# LEDs.net
KiCad netlist of a schematic drawn in Altium Designer
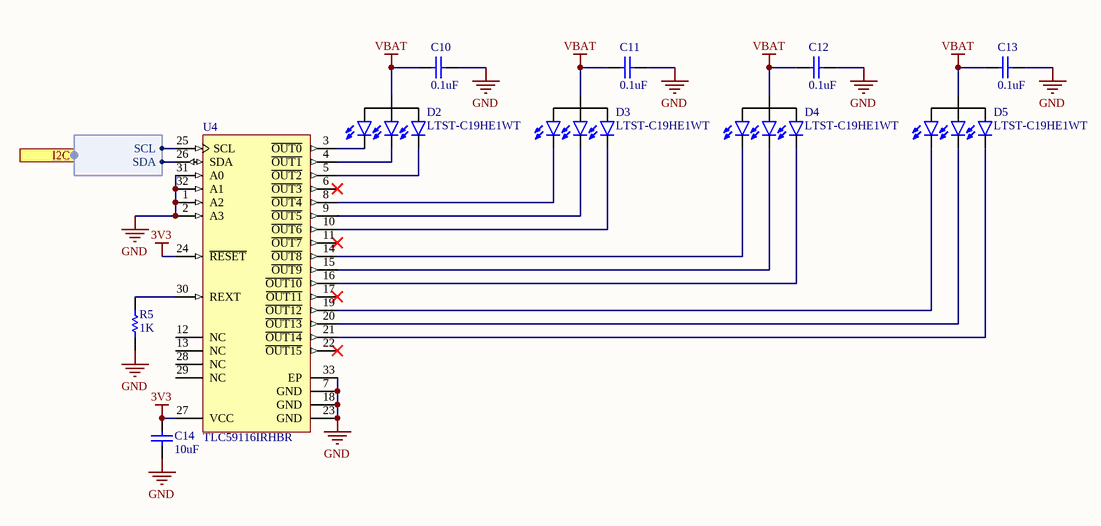
[diagram p0: LEDs.SchDoc]

(export (version "E")
  (design (tool "Eeschema 10.0.6"))
  (components
    (comp (ref "C10")
      (value "0.1uF")
      (footprint "C0402[1005X55]")
      (description "0.1uF 6.3V 10% 0402 (1005 Metric)")
      (fields (field (name "PARTNUMBER") "GRM155R70J104KA01D") (field (name "MANUFACTURER") "Murata"))
      (libsource (lib "Capacitors") (part "CAP_0.1uF_6.3V_0402_10%"))
    )
    (comp (ref "C11")
      (value "0.1uF")
      (footprint "C0402[1005X55]")
      (description "0.1uF 6.3V 10% 0402 (1005 Metric)")
      (fields (field (name "PARTNUMBER") "GRM155R70J104KA01D") (field (name "MANUFACTURER") "Murata"))
      (libsource (lib "Capacitors") (part "CAP_0.1uF_6.3V_0402_10%"))
    )
    (comp (ref "C12")
      (value "0.1uF")
      (footprint "C0402[1005X55]")
      (description "0.1uF 6.3V 10% 0402 (1005 Metric)")
      (fields (field (name "PARTNUMBER") "GRM155R70J104KA01D") (field (name "MANUFACTURER") "Murata"))
      (libsource (lib "Capacitors") (part "CAP_0.1uF_6.3V_0402_10%"))
    )
    (comp (ref "C13")
      (value "0.1uF")
      (footprint "C0402[1005X55]")
      (description "0.1uF 6.3V 10% 0402 (1005 Metric)")
      (fields (field (name "PARTNUMBER") "GRM155R70J104KA01D") (field (name "MANUFACTURER") "Murata"))
      (libsource (lib "Capacitors") (part "CAP_0.1uF_6.3V_0402_10%"))
    )
    (comp (ref "C14")
      (value "10uF")
      (footprint "C0402[1005X55]")
      (description "10uF 6.3V 20% 0402 (1005 Metric)")
      (fields (field (name "PARTNUMBER") "GRM155R60J106ME44D") (field (name "MANUFACTURER") "Murata"))
      (libsource (lib "Capacitors") (part "CAP_10uF_6.3V_0402_20%"))
    )
    (comp (ref "D2")
      (value "LTST-C19HE1WT")
      (footprint "LED0606")
      (fields (field (name "MANUFACTURER") "Lite-On Inc."))
      (libsource (lib "LEDs") (part "LTST-C19HE1WT"))
    )
    (comp (ref "D3")
      (value "LTST-C19HE1WT")
      (footprint "LED0606")
      (fields (field (name "MANUFACTURER") "Lite-On Inc."))
      (libsource (lib "LEDs") (part "LTST-C19HE1WT"))
    )
    (comp (ref "D4")
      (value "LTST-C19HE1WT")
      (footprint "LED0606")
      (fields (field (name "MANUFACTURER") "Lite-On Inc."))
      (libsource (lib "LEDs") (part "LTST-C19HE1WT"))
    )
    (comp (ref "D5")
      (value "LTST-C19HE1WT")
      (footprint "LED0606")
      (fields (field (name "MANUFACTURER") "Lite-On Inc."))
      (libsource (lib "LEDs") (part "LTST-C19HE1WT"))
    )
    (comp (ref "R5")
      (value "1K")
      (footprint "R0402[1005]")
      (description "1K 0.063W 1% 0402 (1005 Metric)")
      (fields (field (name "MANUFACTURER") "KOA Speer") (field (name "PARTNUMBER") "RK73H1ETTP1001F"))
      (libsource (lib "Resistors") (part "RES_1K_0402_1%"))
    )
    (comp (ref "U4")
      (value "TLC59116IRHBR")
      (footprint "VQFN-32")
      (description "IC LED DRVR LIN DIM 120MA 32VQFN")
      (fields (field (name "MANUFACTURER") "Texas Instruments"))
      (libsource (lib "ICs") (part "TLC59116IRHBR"))
    )
  )
  (nets
    (net (code "2") (name "/SCL") (class "Default")
      (node (ref "U4") (pin "25") (pinfunction "SCL_25") (pintype "input"))
    )
    (net (code "3") (name "/SDA") (class "Default")
      (node (ref "U4") (pin "26") (pinfunction "SDA_26") (pintype "bidirectional"))
    )
    (net (code "5") (name "3V3") (class "Default")
      (node (ref "C14") (pin "2") (pinfunction "2_2") (pintype "passive"))
      (node (ref "U4") (pin "24") (pinfunction "~{RESET}_24") (pintype "input"))
      (node (ref "U4") (pin "27") (pinfunction "VCC_27") (pintype "power_in"))
    )
    (net (code "6") (name "GND") (class "Default")
      (node (ref "C10") (pin "2") (pinfunction "2_2") (pintype "passive"))
      (node (ref "C11") (pin "2") (pinfunction "2_2") (pintype "passive"))
      (node (ref "C12") (pin "2") (pinfunction "2_2") (pintype "passive"))
      (node (ref "C13") (pin "2") (pinfunction "2_2") (pintype "passive"))
      (node (ref "C14") (pin "1") (pinfunction "1_1") (pintype "passive"))
      (node (ref "R5") (pin "1") (pinfunction "1_1") (pintype "passive"))
      (node (ref "U4") (pin "1") (pinfunction "A2_1") (pintype "input"))
      (node (ref "U4") (pin "18") (pinfunction "GND_18") (pintype "power_in"))
      (node (ref "U4") (pin "2") (pinfunction "A3_2") (pintype "input"))
      (node (ref "U4") (pin "23") (pinfunction "GND_23") (pintype "power_in"))
      (node (ref "U4") (pin "31") (pinfunction "A0_31") (pintype "input"))
      (node (ref "U4") (pin "32") (pinfunction "A1_32") (pintype "input"))
      (node (ref "U4") (pin "33") (pinfunction "EP_33") (pintype "power_in"))
      (node (ref "U4") (pin "7") (pinfunction "GND_7") (pintype "power_in"))
    )
    (net (code "7") (name "Net-(D2-K_Blue)") (class "Default")
      (node (ref "D2") (pin "3") (pinfunction "K_Blue_3") (pintype "passive"))
      (node (ref "U4") (pin "5") (pinfunction "~{OUT2}_5") (pintype "output"))
    )
    (net (code "8") (name "Net-(D2-K_Green)") (class "Default")
      (node (ref "D2") (pin "2") (pinfunction "K_Green_2") (pintype "passive"))
      (node (ref "U4") (pin "4") (pinfunction "~{OUT1}_4") (pintype "output"))
    )
    (net (code "9") (name "Net-(D2-K_Red)") (class "Default")
      (node (ref "D2") (pin "1") (pinfunction "K_Red_1") (pintype "passive"))
      (node (ref "U4") (pin "3") (pinfunction "~{OUT0}_3") (pintype "output"))
    )
    (net (code "10") (name "Net-(D3-K_Blue)") (class "Default")
      (node (ref "D3") (pin "3") (pinfunction "K_Blue_3") (pintype "passive"))
      (node (ref "U4") (pin "10") (pinfunction "~{OUT6}_10") (pintype "output"))
    )
    (net (code "11") (name "Net-(D3-K_Green)") (class "Default")
      (node (ref "D3") (pin "2") (pinfunction "K_Green_2") (pintype "passive"))
      (node (ref "U4") (pin "9") (pinfunction "~{OUT5}_9") (pintype "output"))
    )
    (net (code "12") (name "Net-(D3-K_Red)") (class "Default")
      (node (ref "D3") (pin "1") (pinfunction "K_Red_1") (pintype "passive"))
      (node (ref "U4") (pin "8") (pinfunction "~{OUT4}_8") (pintype "output"))
    )
    (net (code "13") (name "Net-(D4-K_Blue)") (class "Default")
      (node (ref "D4") (pin "3") (pinfunction "K_Blue_3") (pintype "passive"))
      (node (ref "U4") (pin "16") (pinfunction "~{OUT10}_16") (pintype "output"))
    )
    (net (code "14") (name "Net-(D4-K_Green)") (class "Default")
      (node (ref "D4") (pin "2") (pinfunction "K_Green_2") (pintype "passive"))
      (node (ref "U4") (pin "15") (pinfunction "~{OUT9}_15") (pintype "output"))
    )
    (net (code "15") (name "Net-(D4-K_Red)") (class "Default")
      (node (ref "D4") (pin "1") (pinfunction "K_Red_1") (pintype "passive"))
      (node (ref "U4") (pin "14") (pinfunction "~{OUT8}_14") (pintype "output"))
    )
    (net (code "16") (name "Net-(D5-K_Blue)") (class "Default")
      (node (ref "D5") (pin "3") (pinfunction "K_Blue_3") (pintype "passive"))
      (node (ref "U4") (pin "21") (pinfunction "~{OUT14}_21") (pintype "output"))
    )
    (net (code "17") (name "Net-(D5-K_Green)") (class "Default")
      (node (ref "D5") (pin "2") (pinfunction "K_Green_2") (pintype "passive"))
      (node (ref "U4") (pin "20") (pinfunction "~{OUT13}_20") (pintype "output"))
    )
    (net (code "18") (name "Net-(D5-K_Red)") (class "Default")
      (node (ref "D5") (pin "1") (pinfunction "K_Red_1") (pintype "passive"))
      (node (ref "U4") (pin "19") (pinfunction "~{OUT12}_19") (pintype "output"))
    )
    (net (code "19") (name "Net-(U4-REXT)") (class "Default")
      (node (ref "R5") (pin "2") (pinfunction "2_2") (pintype "passive"))
      (node (ref "U4") (pin "30") (pinfunction "REXT_30") (pintype "input"))
    )
    (net (code "20") (name "VBAT") (class "Default")
      (node (ref "C10") (pin "1") (pinfunction "1_1") (pintype "passive"))
      (node (ref "C11") (pin "1") (pinfunction "1_1") (pintype "passive"))
      (node (ref "C12") (pin "1") (pinfunction "1_1") (pintype "passive"))
      (node (ref "C13") (pin "1") (pinfunction "1_1") (pintype "passive"))
      (node (ref "D2") (pin "4") (pinfunction "A_4") (pintype "passive"))
      (node (ref "D3") (pin "4") (pinfunction "A_4") (pintype "passive"))
      (node (ref "D4") (pin "4") (pinfunction "A_4") (pintype "passive"))
      (node (ref "D5") (pin "4") (pinfunction "A_4") (pintype "passive"))
    )
    (net (code "21") (name "unconnected-(U4-NC-Pad12)") (class "Default")
      (node (ref "U4") (pin "12") (pinfunction "NC_12") (pintype "passive"))
    )
    (net (code "22") (name "unconnected-(U4-NC-Pad13)") (class "Default")
      (node (ref "U4") (pin "13") (pinfunction "NC_13") (pintype "passive"))
    )
    (net (code "23") (name "unconnected-(U4-NC-Pad28)") (class "Default")
      (node (ref "U4") (pin "28") (pinfunction "NC_28") (pintype "passive"))
    )
    (net (code "24") (name "unconnected-(U4-NC-Pad29)") (class "Default")
      (node (ref "U4") (pin "29") (pinfunction "NC_29") (pintype "passive"))
    )
    (net (code "25") (name "unconnected-(U4-~{OUT3}-Pad6)") (class "Default")
      (node (ref "U4") (pin "6") (pinfunction "~{OUT3}_6") (pintype "output+no_connect"))
    )
    (net (code "26") (name "unconnected-(U4-~{OUT7}-Pad11)") (class "Default")
      (node (ref "U4") (pin "11") (pinfunction "~{OUT7}_11") (pintype "output+no_connect"))
    )
    (net (code "27") (name "unconnected-(U4-~{OUT11}-Pad17)") (class "Default")
      (node (ref "U4") (pin "17") (pinfunction "~{OUT11}_17") (pintype "output+no_connect"))
    )
    (net (code "28") (name "unconnected-(U4-~{OUT15}-Pad22)") (class "Default")
      (node (ref "U4") (pin "22") (pinfunction "~{OUT15}_22") (pintype "output+no_connect"))
    )
  )
)
